# HueDot9-RevA.net
KiCad netlist of a schematic drawn in EAGLE
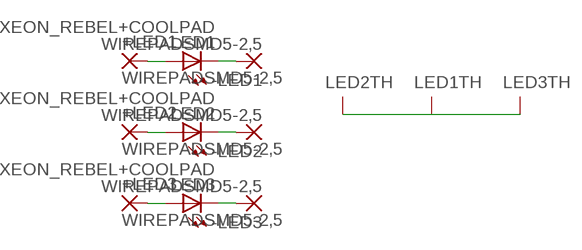
[diagram p0: schematic, sheet 1]

(export (version "E")
  (design (tool "Eeschema 10.0.6"))
  (components
    (comp (ref "+LED1")
      (value "WIREPADSMD5-2,5")
      (footprint "eagle-import:5-2,5")
      (libsource (lib "eagle-import") (part "WIREPADSMD5-2,5"))
    )
    (comp (ref "+LED2")
      (value "WIREPADSMD5-2,5")
      (footprint "eagle-import:5-2,5")
      (libsource (lib "eagle-import") (part "WIREPADSMD5-2,5"))
    )
    (comp (ref "+LED3")
      (value "WIREPADSMD5-2,5")
      (footprint "eagle-import:5-2,5")
      (libsource (lib "eagle-import") (part "WIREPADSMD5-2,5"))
    )
    (comp (ref "-LED1")
      (value "WIREPADSMD5-2,5")
      (footprint "eagle-import:5-2,5")
      (libsource (lib "eagle-import") (part "WIREPADSMD5-2,5"))
    )
    (comp (ref "-LED2")
      (value "WIREPADSMD5-2,5")
      (footprint "eagle-import:5-2,5")
      (libsource (lib "eagle-import") (part "WIREPADSMD5-2,5"))
    )
    (comp (ref "-LED3")
      (value "WIREPADSMD5-2,5")
      (footprint "eagle-import:5-2,5")
      (libsource (lib "eagle-import") (part "WIREPADSMD5-2,5"))
    )
    (comp (ref "LED1")
      (value "LUXEON_REBEL+COOLPAD")
      (footprint "eagle-import:LUXEON_REBEL+COOLPAD")
      (libsource (lib "eagle-import") (part "LUXEON_REBEL+COOLPAD"))
    )
    (comp (ref "LED2")
      (value "LUXEON_REBEL+COOLPAD")
      (footprint "eagle-import:LUXEON_REBEL+COOLPAD")
      (libsource (lib "eagle-import") (part "LUXEON_REBEL+COOLPAD"))
    )
    (comp (ref "LED3")
      (value "LUXEON_REBEL+COOLPAD")
      (footprint "eagle-import:LUXEON_REBEL+COOLPAD")
      (libsource (lib "eagle-import") (part "LUXEON_REBEL+COOLPAD"))
    )
  )
  (nets
    (net (code "1") (name "Net-(+LED1-P)") (class "Default")
      (node (ref "+LED1") (pin "1") (pinfunction "P_1") (pintype "passive"))
      (node (ref "LED1") (pin "A") (pinfunction "A_A") (pintype "passive"))
      (node (ref "LED1") (pin "A@1") (pinfunction "A_A@1") (pintype "passive"))
    )
    (net (code "2") (name "Net-(+LED2-P)") (class "Default")
      (node (ref "+LED2") (pin "1") (pinfunction "P_1") (pintype "passive"))
      (node (ref "LED2") (pin "A") (pinfunction "A_A") (pintype "passive"))
      (node (ref "LED2") (pin "A@1") (pinfunction "A_A@1") (pintype "passive"))
    )
    (net (code "3") (name "Net-(+LED3-P)") (class "Default")
      (node (ref "+LED3") (pin "1") (pinfunction "P_1") (pintype "passive"))
      (node (ref "LED3") (pin "A") (pinfunction "A_A") (pintype "passive"))
      (node (ref "LED3") (pin "A@1") (pinfunction "A_A@1") (pintype "passive"))
    )
    (net (code "4") (name "Net-(-LED1-P)") (class "Default")
      (node (ref "-LED1") (pin "1") (pinfunction "P_1") (pintype "passive"))
      (node (ref "LED1") (pin "C") (pinfunction "C_C") (pintype "passive"))
      (node (ref "LED1") (pin "C@1") (pinfunction "C_C@1") (pintype "passive"))
    )
    (net (code "5") (name "Net-(-LED2-P)") (class "Default")
      (node (ref "-LED2") (pin "1") (pinfunction "P_1") (pintype "passive"))
      (node (ref "LED2") (pin "C") (pinfunction "C_C") (pintype "passive"))
      (node (ref "LED2") (pin "C@1") (pinfunction "C_C@1") (pintype "passive"))
    )
    (net (code "6") (name "Net-(-LED3-P)") (class "Default")
      (node (ref "-LED3") (pin "1") (pinfunction "P_1") (pintype "passive"))
      (node (ref "LED3") (pin "C") (pinfunction "C_C") (pintype "passive"))
      (node (ref "LED3") (pin "C@1") (pinfunction "C_C@1") (pintype "passive"))
    )
    (net (code "7") (name "Net-(LED1-PadTH)") (class "Default")
      (node (ref "LED1") (pin "TH") (pinfunction "TH_TH") (pintype "power_in"))
      (node (ref "LED1") (pin "TH@1") (pinfunction "TH_TH@1") (pintype "power_in"))
      (node (ref "LED1") (pin "TH@10") (pinfunction "TH_TH@10") (pintype "power_in"))
      (node (ref "LED1") (pin "TH@11") (pinfunction "TH_TH@11") (pintype "power_in"))
      (node (ref "LED1") (pin "TH@12") (pinfunction "TH_TH@12") (pintype "power_in"))
      (node (ref "LED1") (pin "TH@13") (pinfunction "TH_TH@13") (pintype "power_in"))
      (node (ref "LED1") (pin "TH@14") (pinfunction "TH_TH@14") (pintype "power_in"))
      (node (ref "LED1") (pin "TH@15") (pinfunction "TH_TH@15") (pintype "power_in"))
      (node (ref "LED1") (pin "TH@16") (pinfunction "TH_TH@16") (pintype "power_in"))
      (node (ref "LED1") (pin "TH@17") (pinfunction "TH_TH@17") (pintype "power_in"))
      (node (ref "LED1") (pin "TH@18") (pinfunction "TH_TH@18") (pintype "power_in"))
      (node (ref "LED1") (pin "TH@19") (pinfunction "TH_TH@19") (pintype "power_in"))
      (node (ref "LED1") (pin "TH@2") (pinfunction "TH_TH@2") (pintype "power_in"))
      (node (ref "LED1") (pin "TH@20") (pinfunction "TH_TH@20") (pintype "power_in"))
      (node (ref "LED1") (pin "TH@21") (pinfunction "TH_TH@21") (pintype "power_in"))
      (node (ref "LED1") (pin "TH@22") (pinfunction "TH_TH@22") (pintype "power_in"))
      (node (ref "LED1") (pin "TH@23") (pinfunction "TH_TH@23") (pintype "power_in"))
      (node (ref "LED1") (pin "TH@24") (pinfunction "TH_TH@24") (pintype "power_in"))
      (node (ref "LED1") (pin "TH@25") (pinfunction "TH_TH@25") (pintype "power_in"))
      (node (ref "LED1") (pin "TH@26") (pinfunction "TH_TH@26") (pintype "power_in"))
      (node (ref "LED1") (pin "TH@27") (pinfunction "TH_TH@27") (pintype "power_in"))
      (node (ref "LED1") (pin "TH@28") (pinfunction "TH_TH@28") (pintype "power_in"))
      (node (ref "LED1") (pin "TH@29") (pinfunction "TH_TH@29") (pintype "power_in"))
      (node (ref "LED1") (pin "TH@3") (pinfunction "TH_TH@3") (pintype "power_in"))
      (node (ref "LED1") (pin "TH@30") (pinfunction "TH_TH@30") (pintype "power_in"))
      (node (ref "LED1") (pin "TH@31") (pinfunction "TH_TH@31") (pintype "power_in"))
      (node (ref "LED1") (pin "TH@32") (pinfunction "TH_TH@32") (pintype "power_in"))
      (node (ref "LED1") (pin "TH@33") (pinfunction "TH_TH@33") (pintype "power_in"))
      (node (ref "LED1") (pin "TH@34") (pinfunction "TH_TH@34") (pintype "power_in"))
      (node (ref "LED1") (pin "TH@35") (pinfunction "TH_TH@35") (pintype "power_in"))
      (node (ref "LED1") (pin "TH@4") (pinfunction "TH_TH@4") (pintype "power_in"))
      (node (ref "LED1") (pin "TH@5") (pinfunction "TH_TH@5") (pintype "power_in"))
      (node (ref "LED1") (pin "TH@6") (pinfunction "TH_TH@6") (pintype "power_in"))
      (node (ref "LED1") (pin "TH@7") (pinfunction "TH_TH@7") (pintype "power_in"))
      (node (ref "LED1") (pin "TH@8") (pinfunction "TH_TH@8") (pintype "power_in"))
      (node (ref "LED1") (pin "TH@9") (pinfunction "TH_TH@9") (pintype "power_in"))
      (node (ref "LED2") (pin "TH") (pinfunction "TH_TH") (pintype "power_in"))
      (node (ref "LED2") (pin "TH@1") (pinfunction "TH_TH@1") (pintype "power_in"))
      (node (ref "LED2") (pin "TH@10") (pinfunction "TH_TH@10") (pintype "power_in"))
      (node (ref "LED2") (pin "TH@11") (pinfunction "TH_TH@11") (pintype "power_in"))
      (node (ref "LED2") (pin "TH@12") (pinfunction "TH_TH@12") (pintype "power_in"))
      (node (ref "LED2") (pin "TH@13") (pinfunction "TH_TH@13") (pintype "power_in"))
      (node (ref "LED2") (pin "TH@14") (pinfunction "TH_TH@14") (pintype "power_in"))
      (node (ref "LED2") (pin "TH@15") (pinfunction "TH_TH@15") (pintype "power_in"))
      (node (ref "LED2") (pin "TH@16") (pinfunction "TH_TH@16") (pintype "power_in"))
      (node (ref "LED2") (pin "TH@17") (pinfunction "TH_TH@17") (pintype "power_in"))
      (node (ref "LED2") (pin "TH@18") (pinfunction "TH_TH@18") (pintype "power_in"))
      (node (ref "LED2") (pin "TH@19") (pinfunction "TH_TH@19") (pintype "power_in"))
      (node (ref "LED2") (pin "TH@2") (pinfunction "TH_TH@2") (pintype "power_in"))
      (node (ref "LED2") (pin "TH@20") (pinfunction "TH_TH@20") (pintype "power_in"))
      (node (ref "LED2") (pin "TH@21") (pinfunction "TH_TH@21") (pintype "power_in"))
      (node (ref "LED2") (pin "TH@22") (pinfunction "TH_TH@22") (pintype "power_in"))
      (node (ref "LED2") (pin "TH@23") (pinfunction "TH_TH@23") (pintype "power_in"))
      (node (ref "LED2") (pin "TH@24") (pinfunction "TH_TH@24") (pintype "power_in"))
      (node (ref "LED2") (pin "TH@25") (pinfunction "TH_TH@25") (pintype "power_in"))
      (node (ref "LED2") (pin "TH@26") (pinfunction "TH_TH@26") (pintype "power_in"))
      (node (ref "LED2") (pin "TH@27") (pinfunction "TH_TH@27") (pintype "power_in"))
      (node (ref "LED2") (pin "TH@28") (pinfunction "TH_TH@28") (pintype "power_in"))
      (node (ref "LED2") (pin "TH@29") (pinfunction "TH_TH@29") (pintype "power_in"))
      (node (ref "LED2") (pin "TH@3") (pinfunction "TH_TH@3") (pintype "power_in"))
      (node (ref "LED2") (pin "TH@30") (pinfunction "TH_TH@30") (pintype "power_in"))
      (node (ref "LED2") (pin "TH@31") (pinfunction "TH_TH@31") (pintype "power_in"))
      (node (ref "LED2") (pin "TH@32") (pinfunction "TH_TH@32") (pintype "power_in"))
      (node (ref "LED2") (pin "TH@33") (pinfunction "TH_TH@33") (pintype "power_in"))
      (node (ref "LED2") (pin "TH@34") (pinfunction "TH_TH@34") (pintype "power_in"))
      (node (ref "LED2") (pin "TH@35") (pinfunction "TH_TH@35") (pintype "power_in"))
      (node (ref "LED2") (pin "TH@4") (pinfunction "TH_TH@4") (pintype "power_in"))
      (node (ref "LED2") (pin "TH@5") (pinfunction "TH_TH@5") (pintype "power_in"))
      (node (ref "LED2") (pin "TH@6") (pinfunction "TH_TH@6") (pintype "power_in"))
      (node (ref "LED2") (pin "TH@7") (pinfunction "TH_TH@7") (pintype "power_in"))
      (node (ref "LED2") (pin "TH@8") (pinfunction "TH_TH@8") (pintype "power_in"))
      (node (ref "LED2") (pin "TH@9") (pinfunction "TH_TH@9") (pintype "power_in"))
      (node (ref "LED3") (pin "TH") (pinfunction "TH_TH") (pintype "power_in"))
      (node (ref "LED3") (pin "TH@1") (pinfunction "TH_TH@1") (pintype "power_in"))
      (node (ref "LED3") (pin "TH@10") (pinfunction "TH_TH@10") (pintype "power_in"))
      (node (ref "LED3") (pin "TH@11") (pinfunction "TH_TH@11") (pintype "power_in"))
      (node (ref "LED3") (pin "TH@12") (pinfunction "TH_TH@12") (pintype "power_in"))
      (node (ref "LED3") (pin "TH@13") (pinfunction "TH_TH@13") (pintype "power_in"))
      (node (ref "LED3") (pin "TH@14") (pinfunction "TH_TH@14") (pintype "power_in"))
      (node (ref "LED3") (pin "TH@15") (pinfunction "TH_TH@15") (pintype "power_in"))
      (node (ref "LED3") (pin "TH@16") (pinfunction "TH_TH@16") (pintype "power_in"))
      (node (ref "LED3") (pin "TH@17") (pinfunction "TH_TH@17") (pintype "power_in"))
      (node (ref "LED3") (pin "TH@18") (pinfunction "TH_TH@18") (pintype "power_in"))
      (node (ref "LED3") (pin "TH@19") (pinfunction "TH_TH@19") (pintype "power_in"))
      (node (ref "LED3") (pin "TH@2") (pinfunction "TH_TH@2") (pintype "power_in"))
      (node (ref "LED3") (pin "TH@20") (pinfunction "TH_TH@20") (pintype "power_in"))
      (node (ref "LED3") (pin "TH@21") (pinfunction "TH_TH@21") (pintype "power_in"))
      (node (ref "LED3") (pin "TH@22") (pinfunction "TH_TH@22") (pintype "power_in"))
      (node (ref "LED3") (pin "TH@23") (pinfunction "TH_TH@23") (pintype "power_in"))
      (node (ref "LED3") (pin "TH@24") (pinfunction "TH_TH@24") (pintype "power_in"))
      (node (ref "LED3") (pin "TH@25") (pinfunction "TH_TH@25") (pintype "power_in"))
      (node (ref "LED3") (pin "TH@26") (pinfunction "TH_TH@26") (pintype "power_in"))
      (node (ref "LED3") (pin "TH@27") (pinfunction "TH_TH@27") (pintype "power_in"))
      (node (ref "LED3") (pin "TH@28") (pinfunction "TH_TH@28") (pintype "power_in"))
      (node (ref "LED3") (pin "TH@29") (pinfunction "TH_TH@29") (pintype "power_in"))
      (node (ref "LED3") (pin "TH@3") (pinfunction "TH_TH@3") (pintype "power_in"))
      (node (ref "LED3") (pin "TH@30") (pinfunction "TH_TH@30") (pintype "power_in"))
      (node (ref "LED3") (pin "TH@31") (pinfunction "TH_TH@31") (pintype "power_in"))
      (node (ref "LED3") (pin "TH@32") (pinfunction "TH_TH@32") (pintype "power_in"))
      (node (ref "LED3") (pin "TH@33") (pinfunction "TH_TH@33") (pintype "power_in"))
      (node (ref "LED3") (pin "TH@34") (pinfunction "TH_TH@34") (pintype "power_in"))
      (node (ref "LED3") (pin "TH@35") (pinfunction "TH_TH@35") (pintype "power_in"))
      (node (ref "LED3") (pin "TH@4") (pinfunction "TH_TH@4") (pintype "power_in"))
      (node (ref "LED3") (pin "TH@5") (pinfunction "TH_TH@5") (pintype "power_in"))
      (node (ref "LED3") (pin "TH@6") (pinfunction "TH_TH@6") (pintype "power_in"))
      (node (ref "LED3") (pin "TH@7") (pinfunction "TH_TH@7") (pintype "power_in"))
      (node (ref "LED3") (pin "TH@8") (pinfunction "TH_TH@8") (pintype "power_in"))
      (node (ref "LED3") (pin "TH@9") (pinfunction "TH_TH@9") (pintype "power_in"))
    )
  )
)
